# uControllerJackInterface.net
KiCad netlist of a schematic drawn in EAGLE
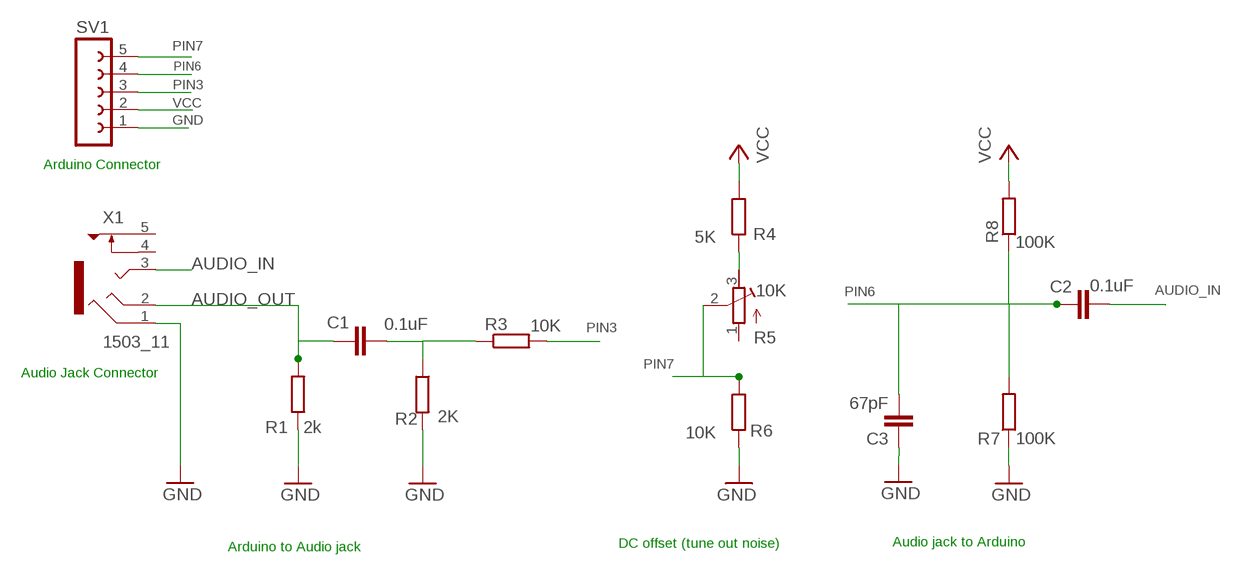
[diagram p0: schematic, sheet 1]

(export (version "E")
  (design (tool "Eeschema 10.0.6"))
  (components
    (comp (ref "C1")
      (value "0.1uF")
      (footprint "eagle-import:C025-025X050")
      (libsource (lib "eagle-import") (part "C-EU025-025X050"))
    )
    (comp (ref "C2")
      (value "0.1uF")
      (footprint "eagle-import:C025-025X050")
      (libsource (lib "eagle-import") (part "C-EU025-025X050"))
    )
    (comp (ref "C3")
      (value "67pF")
      (footprint "eagle-import:C025-025X050")
      (libsource (lib "eagle-import") (part "C-EU025-025X050"))
    )
    (comp (ref "R1")
      (value "2k")
      (footprint "eagle-import:0204_7")
      (libsource (lib "eagle-import") (part "R-EU_0204/7"))
    )
    (comp (ref "R2")
      (value "2K")
      (footprint "eagle-import:0204_7")
      (libsource (lib "eagle-import") (part "R-EU_0204/7"))
    )
    (comp (ref "R3")
      (value "10K")
      (footprint "eagle-import:0204_7")
      (libsource (lib "eagle-import") (part "R-EU_0204/7"))
    )
    (comp (ref "R4")
      (value "5K")
      (footprint "eagle-import:0204_7")
      (libsource (lib "eagle-import") (part "R-EU_0204/7"))
    )
    (comp (ref "R5")
      (value "10K")
      (footprint "eagle-import:RTRIM64Y")
      (libsource (lib "eagle-import") (part "R-TRIMM64Y"))
    )
    (comp (ref "R6")
      (value "10K")
      (footprint "eagle-import:0204_7")
      (libsource (lib "eagle-import") (part "R-EU_0204/7"))
    )
    (comp (ref "R7")
      (value "100K")
      (footprint "eagle-import:0204_7")
      (libsource (lib "eagle-import") (part "R-EU_0204/7"))
    )
    (comp (ref "R8")
      (value "100K")
      (footprint "eagle-import:0204_7")
      (libsource (lib "eagle-import") (part "R-EU_0204/7"))
    )
    (comp (ref "SV1")
      (value "FE05-1")
      (footprint "eagle-import:FE05-1")
      (libsource (lib "eagle-import") (part "FE05-1"))
    )
    (comp (ref "X1")
      (value "1503_11")
      (footprint "eagle-import:1503_11")
      (libsource (lib "eagle-import") (part "1503_11"))
    )
  )
  (nets
    (net (code "1") (name "/AUDIO_IN") (class "Default")
      (node (ref "C2") (pin "2") (pinfunction "2_2") (pintype "passive"))
      (node (ref "X1") (pin "3") (pinfunction "3_3") (pintype "passive"))
    )
    (net (code "2") (name "/AUDIO_OUT") (class "Default")
      (node (ref "C1") (pin "1") (pinfunction "1_1") (pintype "passive"))
      (node (ref "R1") (pin "2") (pinfunction "2_2") (pintype "passive"))
      (node (ref "X1") (pin "2") (pinfunction "2_2") (pintype "passive"))
    )
    (net (code "3") (name "/PIN3") (class "Default")
      (node (ref "R3") (pin "2") (pinfunction "2_2") (pintype "passive"))
      (node (ref "SV1") (pin "3") (pinfunction "3_3") (pintype "passive"))
    )
    (net (code "4") (name "/PIN6") (class "Default")
      (node (ref "C2") (pin "1") (pinfunction "1_1") (pintype "passive"))
      (node (ref "C3") (pin "2") (pinfunction "2_2") (pintype "passive"))
      (node (ref "R7") (pin "2") (pinfunction "2_2") (pintype "passive"))
      (node (ref "R8") (pin "1") (pinfunction "1_1") (pintype "passive"))
      (node (ref "SV1") (pin "4") (pinfunction "4_4") (pintype "passive"))
    )
    (net (code "5") (name "/PIN7") (class "Default")
      (node (ref "R5") (pin "2") (pinfunction "S_2") (pintype "passive"))
      (node (ref "R6") (pin "2") (pinfunction "2_2") (pintype "passive"))
      (node (ref "SV1") (pin "5") (pinfunction "5_5") (pintype "passive"))
    )
    (net (code "6") (name "GND") (class "Default")
      (node (ref "C3") (pin "1") (pinfunction "1_1") (pintype "passive"))
      (node (ref "R1") (pin "1") (pinfunction "1_1") (pintype "passive"))
      (node (ref "R2") (pin "2") (pinfunction "2_2") (pintype "passive"))
      (node (ref "R6") (pin "1") (pinfunction "1_1") (pintype "passive"))
      (node (ref "R7") (pin "1") (pinfunction "1_1") (pintype "passive"))
      (node (ref "SV1") (pin "1") (pinfunction "1_1") (pintype "passive"))
      (node (ref "X1") (pin "1") (pinfunction "1_1") (pintype "passive"))
    )
    (net (code "7") (name "Net-(C1-Pad2)") (class "Default")
      (node (ref "C1") (pin "2") (pinfunction "2_2") (pintype "passive"))
      (node (ref "R2") (pin "1") (pinfunction "1_1") (pintype "passive"))
      (node (ref "R3") (pin "1") (pinfunction "1_1") (pintype "passive"))
    )
    (net (code "8") (name "Net-(R5-E)") (class "Default")
      (node (ref "R4") (pin "1") (pinfunction "1_1") (pintype "passive"))
      (node (ref "R5") (pin "3") (pinfunction "E_3") (pintype "passive"))
    )
    (net (code "9") (name "VCC") (class "Default")
      (node (ref "R4") (pin "2") (pinfunction "2_2") (pintype "passive"))
      (node (ref "R8") (pin "2") (pinfunction "2_2") (pintype "passive"))
      (node (ref "SV1") (pin "2") (pinfunction "2_2") (pintype "passive"))
    )
    (net (code "10") (name "unconnected-(R5-A-Pad1)") (class "Default")
      (node (ref "R5") (pin "1") (pinfunction "A_1") (pintype "passive"))
    )
    (net (code "11") (name "unconnected-(X1-Pad4)") (class "Default")
      (node (ref "X1") (pin "4") (pinfunction "4_4") (pintype "passive"))
    )
    (net (code "12") (name "unconnected-(X1-Pad5)") (class "Default")
      (node (ref "X1") (pin "5") (pinfunction "5_5") (pintype "passive"))
    )
  )
)
